# rev-sensor.net
KiCad netlist of a schematic drawn in EAGLE
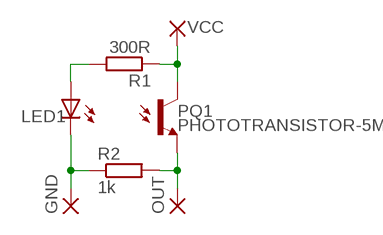
[diagram p0: schematic, sheet 1]

(export (version "E")
  (design (tool "Eeschema 10.0.6"))
  (components
    (comp (ref "GND")
      (value "WIREPADSMD5-1,8")
      (footprint "eagle-import:5-1,8")
      (libsource (lib "eagle-import") (part "WIREPADSMD5-1,8"))
    )
    (comp (ref "LED1")
      (value "LED5MM")
      (footprint "eagle-import:LED5MM")
      (libsource (lib "eagle-import") (part "LED5MM"))
    )
    (comp (ref "OUT")
      (value "WIREPADSMD5-1,8")
      (footprint "eagle-import:5-1,8")
      (libsource (lib "eagle-import") (part "WIREPADSMD5-1,8"))
    )
    (comp (ref "PQ1")
      (value "PHOTOTRANSISTOR-5MM")
      (footprint "eagle-import:LED5MM")
      (libsource (lib "eagle-import") (part "PHOTOTRANSISTOR-5MM"))
    )
    (comp (ref "R1")
      (value "300R")
      (footprint "eagle-import:R0805")
      (libsource (lib "eagle-import") (part "R-EU_R0805"))
    )
    (comp (ref "R2")
      (value "1k")
      (footprint "eagle-import:R0805")
      (libsource (lib "eagle-import") (part "R-EU_R0805"))
    )
    (comp (ref "VCC")
      (value "WIREPADSMD5-1,8")
      (footprint "eagle-import:5-1,8")
      (libsource (lib "eagle-import") (part "WIREPADSMD5-1,8"))
    )
  )
  (nets
    (net (code "1") (name "Net-(GND-P)") (class "Default")
      (node (ref "GND") (pin "1") (pinfunction "P_1") (pintype "passive"))
      (node (ref "LED1") (pin "K") (pinfunction "C_K") (pintype "passive"))
      (node (ref "R2") (pin "1") (pinfunction "1_1") (pintype "passive"))
    )
    (net (code "2") (name "Net-(LED1-PadA)") (class "Default")
      (node (ref "LED1") (pin "A") (pinfunction "A_A") (pintype "passive"))
      (node (ref "R1") (pin "2") (pinfunction "2_2") (pintype "passive"))
    )
    (net (code "3") (name "Net-(OUT-P)") (class "Default")
      (node (ref "OUT") (pin "1") (pinfunction "P_1") (pintype "passive"))
      (node (ref "PQ1") (pin "A") (pinfunction "E_A") (pintype "passive"))
      (node (ref "R2") (pin "2") (pinfunction "2_2") (pintype "passive"))
    )
    (net (code "4") (name "Net-(PQ1-C)") (class "Default")
      (node (ref "PQ1") (pin "K") (pinfunction "C_K") (pintype "passive"))
      (node (ref "R1") (pin "1") (pinfunction "1_1") (pintype "passive"))
      (node (ref "VCC") (pin "1") (pinfunction "P_1") (pintype "passive"))
    )
  )
)
